# GT_16u2_Rev2.net
KiCad netlist of a schematic drawn in Altium Designer
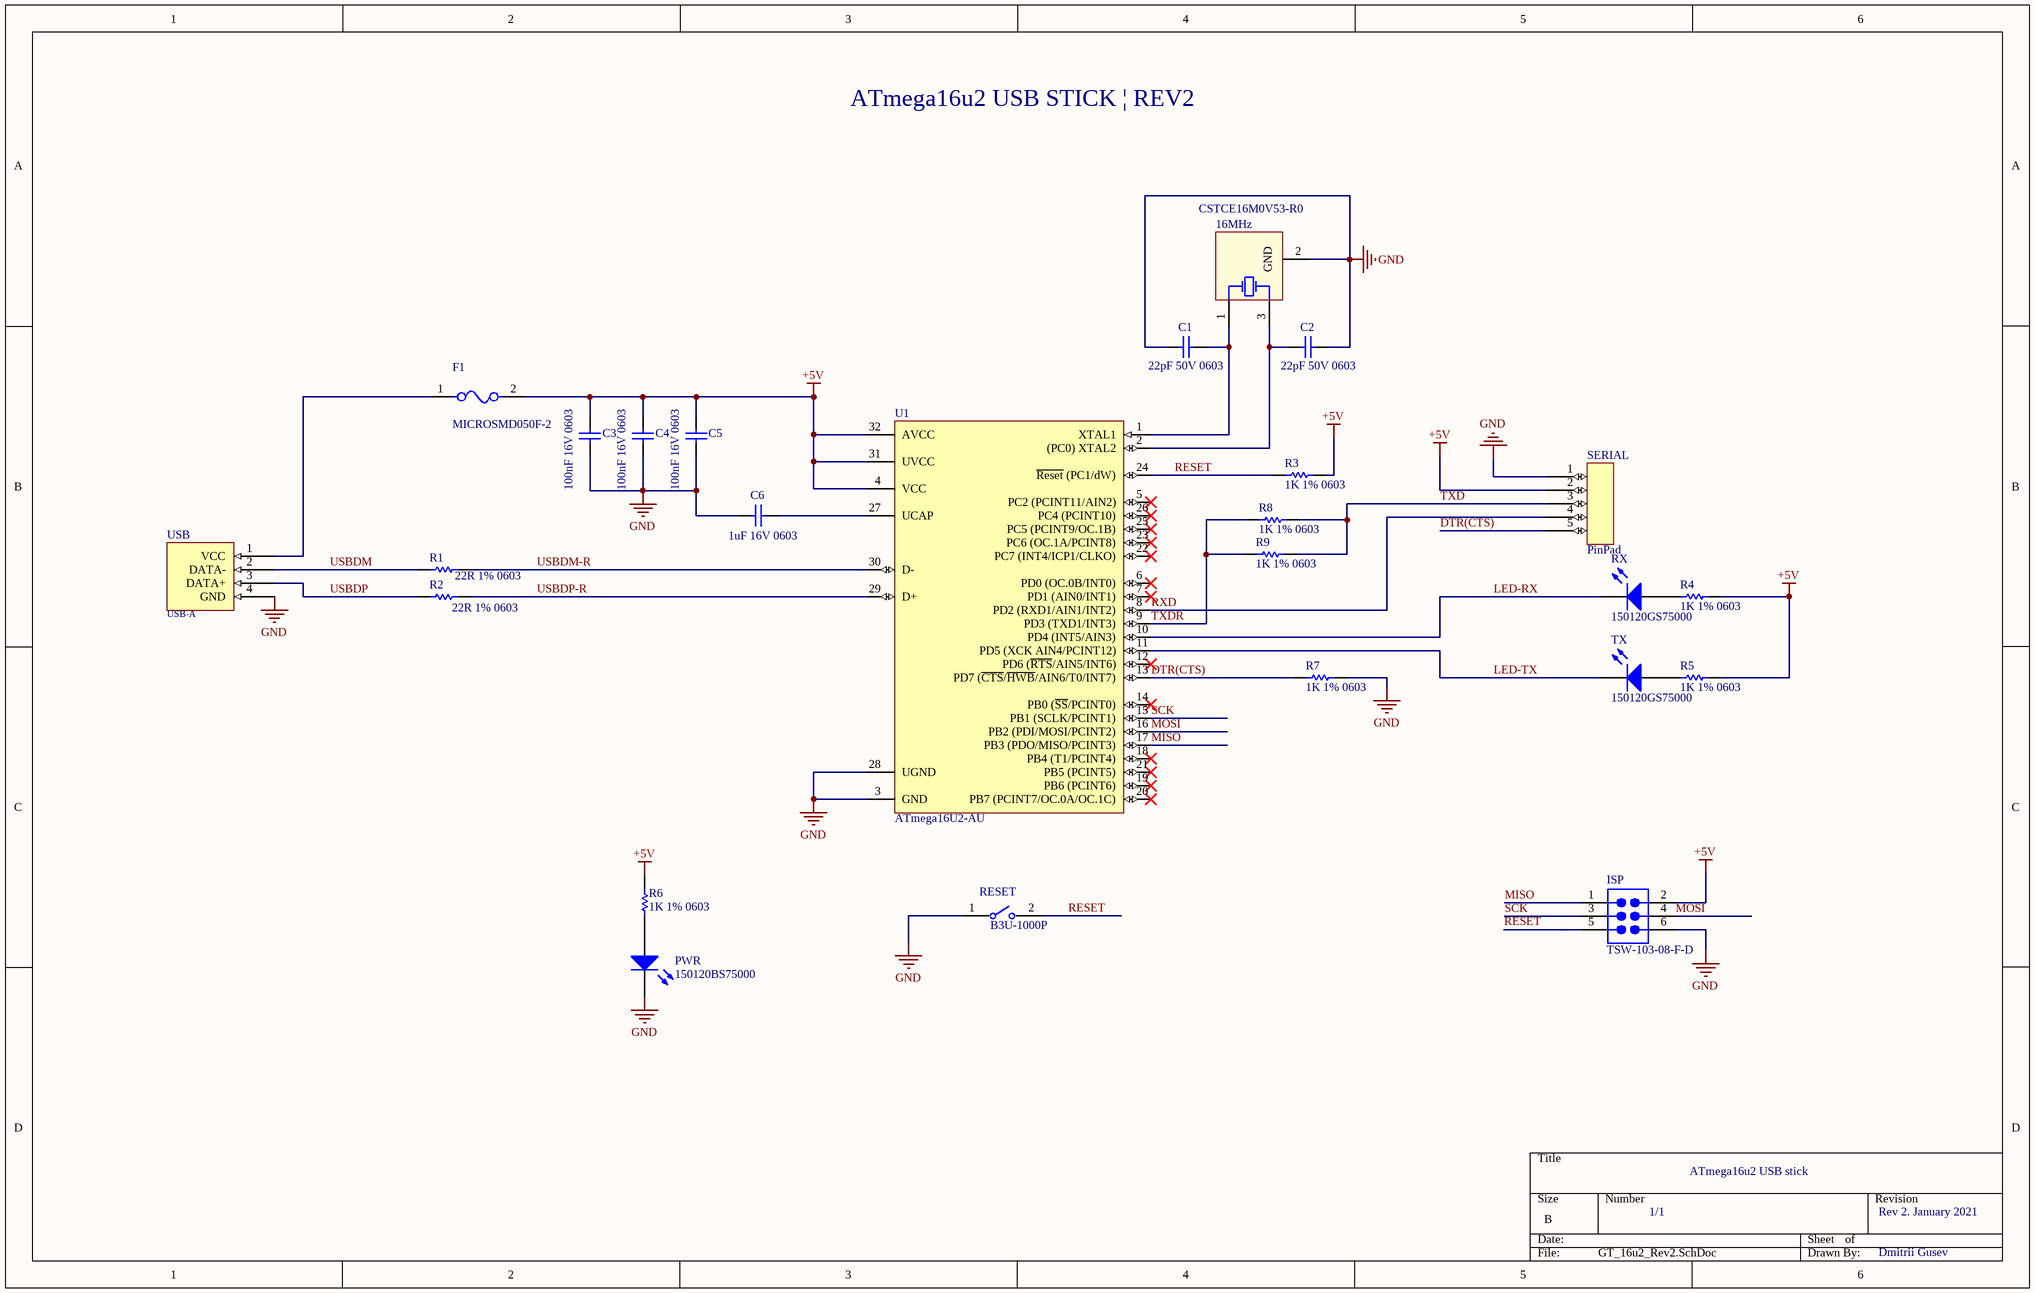
[diagram p0: GT_16u2_Rev2.SchDoc]

(export (version "E")
  (design (tool "Eeschema 10.0.6"))
  (components
    (comp (ref "16MHz")
      (value "CSTCE16M0V53-R0")
      (footprint "MURA-CSTCE_V-3_V")
      (fields (field (name "MANUFACTURER") "Murata"))
      (libsource (lib "Altium Content Vault") (part "MURA-CSTCE_V-3"))
    )
    (comp (ref "C1")
      (value "22pF 50V 0603")
      (footprint "CAPC1608X90X40ML10T20")
      (description "Chip Capacitor, 22 pF, +/- 5%, 50 V, -55 to 125 degC, 0603 (1608 Metric), RoHS, Tape and Reel")
      (libsource (lib "Altium Content Vault") (part "CAP-NP-2"))
    )
    (comp (ref "C2")
      (value "22pF 50V 0603")
      (footprint "CAPC1608X90X40ML10T20")
      (description "Chip Capacitor, 22 pF, +/- 5%, 50 V, -55 to 125 degC, 0603 (1608 Metric), RoHS, Tape and Reel")
      (libsource (lib "Altium Content Vault") (part "CAP-NP-2"))
    )
    (comp (ref "C3")
      (value "100nF 16V 0603")
      (footprint "CAPC1608X90X35ML15T15")
      (fields
        (field (name "MANUFACTURER") "AVX Interconnect / Elco")
        (field (name "PART NUMBER") "0603YC104KAZ2A")
      )
      (libsource (lib "Altium Content Vault") (part "CAP"))
    )
    (comp (ref "C4")
      (value "100nF 16V 0603")
      (footprint "CAPC1608X90X35ML15T15")
      (fields
        (field (name "MANUFACTURER") "AVX Interconnect / Elco")
        (field (name "PART NUMBER") "0603YC104KAZ2A")
      )
      (libsource (lib "Altium Content Vault") (part "CAP"))
    )
    (comp (ref "C5")
      (value "100nF 16V 0603")
      (footprint "CAPC1608X90X35ML15T15")
      (fields
        (field (name "MANUFACTURER") "AVX Interconnect / Elco")
        (field (name "PART NUMBER") "0603YC104KAZ2A")
      )
      (libsource (lib "Altium Content Vault") (part "CAP"))
    )
    (comp (ref "C6")
      (value "1uF 16V 0603")
      (footprint "CAPC1608X90X35LL15T15")
      (fields
        (field (name "MANUFACTURER") "AVX Interconnect / Elco")
        (field (name "PART NUMBER") "0603YD105KAT2A")
      )
      (libsource (lib "Altium Content Vault") (part "CAP"))
    )
    (comp (ref "F1")
      (value "MICROSMD050F-2")
      (footprint "FP-microSMD-MFG")
      (description "PTC RESET FUSE 13.2V 500MA 1210")
      (fields
        (field (name "MANUFACTURER") "Littelfuse")
        (field (name "OCTOPART") "https://octopart.com/microsmd050f-2-littelfuse-74214982")
      )
      (libsource (lib "Altium Content Vault") (part "5bcf9b9f640e542cf0359d10258e979"))
    )
    (comp (ref "ISP")
      (value "TSW-103-08-F-D")
      (footprint "SMTC-TSW-103-08-X-D")
      (fields (field (name "MANUFACTURER") "Samtec"))
      (libsource (lib "Altium Content Vault") (part "SMTC-TSW-103-08-X-D"))
    )
    (comp (ref "PWR")
      (value "150120BS75000")
      (footprint "1206_A")
      (description "SMD mono-color Chip LED, WL-SMCW, Blue")
      (fields (field (name "MANUFACTURER") "Wuerth Elektronik"))
      (libsource (lib "Altium Content Vault") (part "WE-LED_K1A2-2"))
    )
    (comp (ref "R1")
      (value "22R 1% 0603")
      (footprint "RESC1608X55X25NL10T15")
      (description "Chip Resistor, 22 Ohm, +/- 1%, 0.1 W, -55 to 155 degC, 0603 (1608 Metric), RoHS, Tape and Reel")
      (libsource (lib "Altium Content Vault") (part "RES-2"))
    )
    (comp (ref "R2")
      (value "22R 1% 0603")
      (footprint "RESC1608X55X25NL10T15")
      (description "Chip Resistor, 22 Ohm, +/- 1%, 0.1 W, -55 to 155 degC, 0603 (1608 Metric), RoHS, Tape and Reel")
      (libsource (lib "Altium Content Vault") (part "RES-2"))
    )
    (comp (ref "R3")
      (value "1K 1% 0603")
      (footprint "RESC0603(1608)_L")
      (description "1K 0.1W 5% 0603 (1608 Metric)  SMD")
      (fields (field (name "TOLERANCE") "5 %") (field (name "POWER") "0.1 W"))
      (libsource (lib "Altium Content Vault") (part "RES"))
    )
    (comp (ref "R4")
      (value "1K 1% 0603")
      (footprint "RESC0603(1608)_L")
      (description "1K 0.1W 5% 0603 (1608 Metric)  SMD")
      (fields (field (name "TOLERANCE") "5 %") (field (name "POWER") "0.1 W"))
      (libsource (lib "Altium Content Vault") (part "RES"))
    )
    (comp (ref "R5")
      (value "1K 1% 0603")
      (footprint "RESC0603(1608)_L")
      (description "1K 0.1W 5% 0603 (1608 Metric)  SMD")
      (fields (field (name "TOLERANCE") "5 %") (field (name "POWER") "0.1 W"))
      (libsource (lib "Altium Content Vault") (part "RES"))
    )
    (comp (ref "R6")
      (value "1K 1% 0603")
      (footprint "RESC0603(1608)_L")
      (description "1K 0.1W 5% 0603 (1608 Metric)  SMD")
      (fields (field (name "TOLERANCE") "5 %") (field (name "POWER") "0.1 W"))
      (libsource (lib "Altium Content Vault") (part "RES"))
    )
    (comp (ref "R7")
      (value "1K 1% 0603")
      (footprint "RESC0603(1608)_L")
      (description "1K 0.1W 5% 0603 (1608 Metric)  SMD")
      (fields (field (name "TOLERANCE") "5 %") (field (name "POWER") "0.1 W"))
      (libsource (lib "Altium Content Vault") (part "RES"))
    )
    (comp (ref "R8")
      (value "1K 1% 0603")
      (footprint "RESC0603(1608)_L")
      (description "1K 0.1W 5% 0603 (1608 Metric)  SMD")
      (fields (field (name "TOLERANCE") "5 %") (field (name "POWER") "0.1 W"))
      (libsource (lib "Altium Content Vault") (part "RES"))
    )
    (comp (ref "R9")
      (value "1K 1% 0603")
      (footprint "RESC0603(1608)_L")
      (description "1K 0.1W 5% 0603 (1608 Metric)  SMD")
      (fields (field (name "TOLERANCE") "5 %") (field (name "POWER") "0.1 W"))
      (libsource (lib "Altium Content Vault") (part "RES"))
    )
    (comp (ref "RESET")
      (value "B3U-1000P")
      (footprint "FP-B3U-1000P-MFG")
      (description "SWITCH TACTILE SPST-NO 0.05A 12V")
      (libsource (lib "Altium Content Vault") (part "ae622034201233ca1abcedc05908f33"))
    )
    (comp (ref "RX")
      (value "150120GS75000")
      (footprint "1206_A")
      (description "SMD mono-color Chip LED, WL-SMCW, Green")
      (fields (field (name "MANUFACTURER") "Wuerth Elektronik"))
      (libsource (lib "Altium Content Vault") (part "WE-LED_K1A2-2"))
    )
    (comp (ref "SERIAL")
      (value "PinPad")
      (footprint "PinPad")
      (libsource (lib "GT_16u2_Rev2") (part "PinPad"))
    )
    (comp (ref "TX")
      (value "150120GS75000")
      (footprint "1206_A")
      (description "SMD mono-color Chip LED, WL-SMCW, Green")
      (fields (field (name "MANUFACTURER") "Wuerth Elektronik"))
      (libsource (lib "Altium Content Vault") (part "WE-LED_K1A2-2"))
    )
    (comp (ref "U1")
      (value "ATmega16U2-AU")
      (footprint "32A_M")
      (libsource (lib "Altium Content Vault") (part "MC-8B-ATM8U2-SQ32"))
    )
    (comp (ref "USB") (value "USB-A") (footprint "USB A") (libsource (lib "MSE310_PID") (part "USB-A")))
  )
  (nets
    (net (code "1") (name "+5V") (class "Default")
      (node (ref "C3") (pin "2") (pinfunction "2_2") (pintype "passive"))
      (node (ref "C4") (pin "2") (pinfunction "2_2") (pintype "passive"))
      (node (ref "C5") (pin "2") (pinfunction "2_2") (pintype "passive"))
      (node (ref "F1") (pin "2") (pinfunction "2_2") (pintype "passive"))
      (node (ref "ISP") (pin "2") (pinfunction "2_2") (pintype "passive"))
      (node (ref "R3") (pin "2") (pinfunction "2_2") (pintype "passive"))
      (node (ref "R4") (pin "2") (pinfunction "2_2") (pintype "passive"))
      (node (ref "R5") (pin "2") (pinfunction "2_2") (pintype "passive"))
      (node (ref "R6") (pin "2") (pinfunction "2_2") (pintype "passive"))
      (node (ref "SERIAL") (pin "2") (pintype "bidirectional"))
      (node (ref "U1") (pin "31") (pinfunction "UVCC_31") (pintype "power_in"))
      (node (ref "U1") (pin "32") (pinfunction "AVCC_32") (pintype "power_in"))
      (node (ref "U1") (pin "4") (pinfunction "VCC_4") (pintype "power_in"))
    )
    (net (code "2") (name "/DTR(CTS)") (class "Default")
      (node (ref "R7") (pin "2") (pinfunction "2_2") (pintype "passive"))
      (node (ref "SERIAL") (pin "5") (pintype "bidirectional"))
      (node (ref "U1") (pin "13") (pinfunction "PD7_(~{CTS}/~{HWB}/AIN6/T0/INT7)_13") (pintype "bidirectional"))
    )
    (net (code "3") (name "/LED-RX") (class "Default")
      (node (ref "RX") (pin "1") (pinfunction "K_1") (pintype "passive"))
      (node (ref "U1") (pin "10") (pinfunction "PD4_(INT5/AIN3)_10") (pintype "bidirectional"))
    )
    (net (code "4") (name "/LED-TX") (class "Default")
      (node (ref "TX") (pin "1") (pinfunction "K_1") (pintype "passive"))
      (node (ref "U1") (pin "11") (pinfunction "PD5_(XCK_AIN4/PCINT12)_11") (pintype "bidirectional"))
    )
    (net (code "5") (name "/MISO") (class "Default")
      (node (ref "ISP") (pin "1") (pinfunction "1_1") (pintype "passive"))
      (node (ref "U1") (pin "17") (pinfunction "PB3_(PDO/MISO/PCINT3)_17") (pintype "bidirectional"))
    )
    (net (code "6") (name "/MOSI") (class "Default")
      (node (ref "ISP") (pin "4") (pinfunction "4_4") (pintype "passive"))
      (node (ref "U1") (pin "16") (pinfunction "PB2_(PDI/MOSI/PCINT2)_16") (pintype "bidirectional"))
    )
    (net (code "7") (name "/RESET") (class "Default")
      (node (ref "ISP") (pin "5") (pinfunction "5_5") (pintype "passive"))
      (node (ref "R3") (pin "1") (pinfunction "1_1") (pintype "passive"))
      (node (ref "RESET") (pin "2") (pinfunction "2_2") (pintype "passive"))
      (node (ref "U1") (pin "24") (pinfunction "~{Reset}_(PC1/dW)_24") (pintype "bidirectional"))
    )
    (net (code "8") (name "/RXD") (class "Default")
      (node (ref "SERIAL") (pin "4") (pintype "bidirectional"))
      (node (ref "U1") (pin "8") (pinfunction "PD2_(RXD1/AIN1/INT2)_8") (pintype "bidirectional"))
    )
    (net (code "9") (name "/SCK") (class "Default")
      (node (ref "ISP") (pin "3") (pinfunction "3_3") (pintype "passive"))
      (node (ref "U1") (pin "15") (pinfunction "PB1_(SCLK/PCINT1)_15") (pintype "bidirectional"))
    )
    (net (code "10") (name "/TXD") (class "Default")
      (node (ref "R8") (pin "2") (pinfunction "2_2") (pintype "passive"))
      (node (ref "R9") (pin "2") (pinfunction "2_2") (pintype "passive"))
      (node (ref "SERIAL") (pin "3") (pintype "bidirectional"))
    )
    (net (code "11") (name "/TXDR") (class "Default")
      (node (ref "R8") (pin "1") (pinfunction "1_1") (pintype "passive"))
      (node (ref "R9") (pin "1") (pinfunction "1_1") (pintype "passive"))
      (node (ref "U1") (pin "9") (pinfunction "PD3_(TXD1/INT3)_9") (pintype "bidirectional"))
    )
    (net (code "12") (name "/USBDM") (class "Default")
      (node (ref "R1") (pin "1") (pinfunction "1_1") (pintype "passive"))
      (node (ref "USB") (pin "2") (pinfunction "DATA-_2") (pintype "input"))
    )
    (net (code "13") (name "/USBDM-R") (class "Default")
      (node (ref "R1") (pin "2") (pinfunction "2_2") (pintype "passive"))
      (node (ref "U1") (pin "30") (pinfunction "D-_30") (pintype "bidirectional"))
    )
    (net (code "14") (name "/USBDP") (class "Default")
      (node (ref "R2") (pin "1") (pinfunction "1_1") (pintype "passive"))
      (node (ref "USB") (pin "3") (pinfunction "DATA+_3") (pintype "input"))
    )
    (net (code "15") (name "/USBDP-R") (class "Default")
      (node (ref "R2") (pin "2") (pinfunction "2_2") (pintype "passive"))
      (node (ref "U1") (pin "29") (pinfunction "D+_29") (pintype "bidirectional"))
    )
    (net (code "16") (name "GND") (class "Default")
      (node (ref "16MHz") (pin "2") (pinfunction "GND_2") (pintype "power_in"))
      (node (ref "C1") (pin "2") (pinfunction "2_2") (pintype "passive"))
      (node (ref "C2") (pin "1") (pinfunction "1_1") (pintype "passive"))
      (node (ref "C3") (pin "1") (pinfunction "1_1") (pintype "passive"))
      (node (ref "C4") (pin "1") (pinfunction "1_1") (pintype "passive"))
      (node (ref "C5") (pin "1") (pinfunction "1_1") (pintype "passive"))
      (node (ref "C6") (pin "1") (pinfunction "1_1") (pintype "passive"))
      (node (ref "ISP") (pin "6") (pinfunction "6_6") (pintype "passive"))
      (node (ref "PWR") (pin "1") (pinfunction "K_1") (pintype "passive"))
      (node (ref "R7") (pin "1") (pinfunction "1_1") (pintype "passive"))
      (node (ref "RESET") (pin "1") (pinfunction "1_1") (pintype "passive"))
      (node (ref "SERIAL") (pin "1") (pintype "bidirectional"))
      (node (ref "U1") (pin "28") (pinfunction "UGND_28") (pintype "power_in"))
      (node (ref "U1") (pin "3") (pinfunction "GND_3") (pintype "power_in"))
      (node (ref "USB") (pin "4") (pinfunction "GND_4") (pintype "input"))
    )
    (net (code "17") (name "Net-(16MHz-C1)") (class "Default")
      (node (ref "16MHz") (pin "1") (pinfunction "C1_1") (pintype "passive"))
      (node (ref "C1") (pin "1") (pinfunction "1_1") (pintype "passive"))
      (node (ref "U1") (pin "1") (pinfunction "XTAL1_1") (pintype "input"))
    )
    (net (code "18") (name "Net-(16MHz-C2)") (class "Default")
      (node (ref "16MHz") (pin "3") (pinfunction "C2_3") (pintype "passive"))
      (node (ref "C2") (pin "2") (pinfunction "2_2") (pintype "passive"))
      (node (ref "U1") (pin "2") (pinfunction "(PC0)_XTAL2_2") (pintype "bidirectional"))
    )
    (net (code "19") (name "Net-(PWR-A)") (class "Default")
      (node (ref "PWR") (pin "2") (pinfunction "A_2") (pintype "passive"))
      (node (ref "R6") (pin "1") (pinfunction "1_1") (pintype "passive"))
    )
    (net (code "20") (name "Net-(RX-A)") (class "Default")
      (node (ref "R4") (pin "1") (pinfunction "1_1") (pintype "passive"))
      (node (ref "RX") (pin "2") (pinfunction "A_2") (pintype "passive"))
    )
    (net (code "21") (name "Net-(TX-A)") (class "Default")
      (node (ref "R5") (pin "1") (pinfunction "1_1") (pintype "passive"))
      (node (ref "TX") (pin "2") (pinfunction "A_2") (pintype "passive"))
    )
    (net (code "22") (name "Net-(U1-UCAP)") (class "Default")
      (node (ref "C6") (pin "2") (pinfunction "2_2") (pintype "passive"))
      (node (ref "U1") (pin "27") (pinfunction "UCAP_27") (pintype "power_in"))
    )
    (net (code "23") (name "Net-(USB-VCC)") (class "Default")
      (node (ref "F1") (pin "1") (pinfunction "1_1") (pintype "passive"))
      (node (ref "USB") (pin "1") (pinfunction "VCC_1") (pintype "input"))
    )
    (net (code "24") (name "unconnected-(U1-PB0_(~{SS}{slash}PCINT0)-Pad14)") (class "Default")
      (node (ref "U1") (pin "14") (pinfunction "PB0_(~{SS}/PCINT0)_14") (pintype "bidirectional+no_connect"))
    )
    (net (code "25") (name "unconnected-(U1-PB4_(T1{slash}PCINT4)-Pad18)") (class "Default")
      (node (ref "U1") (pin "18") (pinfunction "PB4_(T1/PCINT4)_18") (pintype "bidirectional+no_connect"))
    )
    (net (code "26") (name "unconnected-(U1-PB5_(PCINT5)-Pad21)") (class "Default")
      (node (ref "U1") (pin "21") (pinfunction "PB5_(PCINT5)_21") (pintype "bidirectional+no_connect"))
    )
    (net (code "27") (name "unconnected-(U1-PB6_(PCINT6)-Pad19)") (class "Default")
      (node (ref "U1") (pin "19") (pinfunction "PB6_(PCINT6)_19") (pintype "bidirectional+no_connect"))
    )
    (net (code "28") (name "unconnected-(U1-PB7_(PCINT7{slash}OC.0A{slash}OC.1C)-Pad20)") (class "Default")
      (node (ref "U1") (pin "20") (pinfunction "PB7_(PCINT7/OC.0A/OC.1C)_20") (pintype "bidirectional+no_connect"))
    )
    (net (code "29") (name "unconnected-(U1-PC2_(PCINT11{slash}AIN2)-Pad5)") (class "Default")
      (node (ref "U1") (pin "5") (pinfunction "PC2_(PCINT11/AIN2)_5") (pintype "bidirectional+no_connect"))
    )
    (net (code "30") (name "unconnected-(U1-PC4_(PCINT10)-Pad26)") (class "Default")
      (node (ref "U1") (pin "26") (pinfunction "PC4_(PCINT10)_26") (pintype "bidirectional+no_connect"))
    )
    (net (code "31") (name "unconnected-(U1-PC5_(PCINT9{slash}OC.1B)-Pad25)") (class "Default")
      (node (ref "U1") (pin "25") (pinfunction "PC5_(PCINT9/OC.1B)_25") (pintype "bidirectional+no_connect"))
    )
    (net (code "32") (name "unconnected-(U1-PC6_(OC.1A{slash}PCINT8)-Pad23)") (class "Default")
      (node (ref "U1") (pin "23") (pinfunction "PC6_(OC.1A/PCINT8)_23") (pintype "bidirectional+no_connect"))
    )
    (net (code "33") (name "unconnected-(U1-PC7_(INT4{slash}ICP1{slash}CLKO)-Pad22)") (class "Default")
      (node (ref "U1") (pin "22") (pinfunction "PC7_(INT4/ICP1/CLKO)_22") (pintype "bidirectional+no_connect"))
    )
    (net (code "34") (name "unconnected-(U1-PD0_(OC.0B{slash}INT0)-Pad6)") (class "Default")
      (node (ref "U1") (pin "6") (pinfunction "PD0_(OC.0B/INT0)_6") (pintype "bidirectional+no_connect"))
    )
    (net (code "35") (name "unconnected-(U1-PD1_(AIN0{slash}INT1)-Pad7)") (class "Default")
      (node (ref "U1") (pin "7") (pinfunction "PD1_(AIN0/INT1)_7") (pintype "bidirectional+no_connect"))
    )
    (net (code "36") (name "unconnected-(U1-PD6_(~{RTS}{slash}AIN5{slash}INT6)-Pad12)") (class "Default")
      (node (ref "U1") (pin "12") (pinfunction "PD6_(~{RTS}/AIN5/INT6)_12") (pintype "bidirectional+no_connect"))
    )
  )
)
